# 15_PMU.net
KiCad netlist of a schematic drawn in Altium Designer
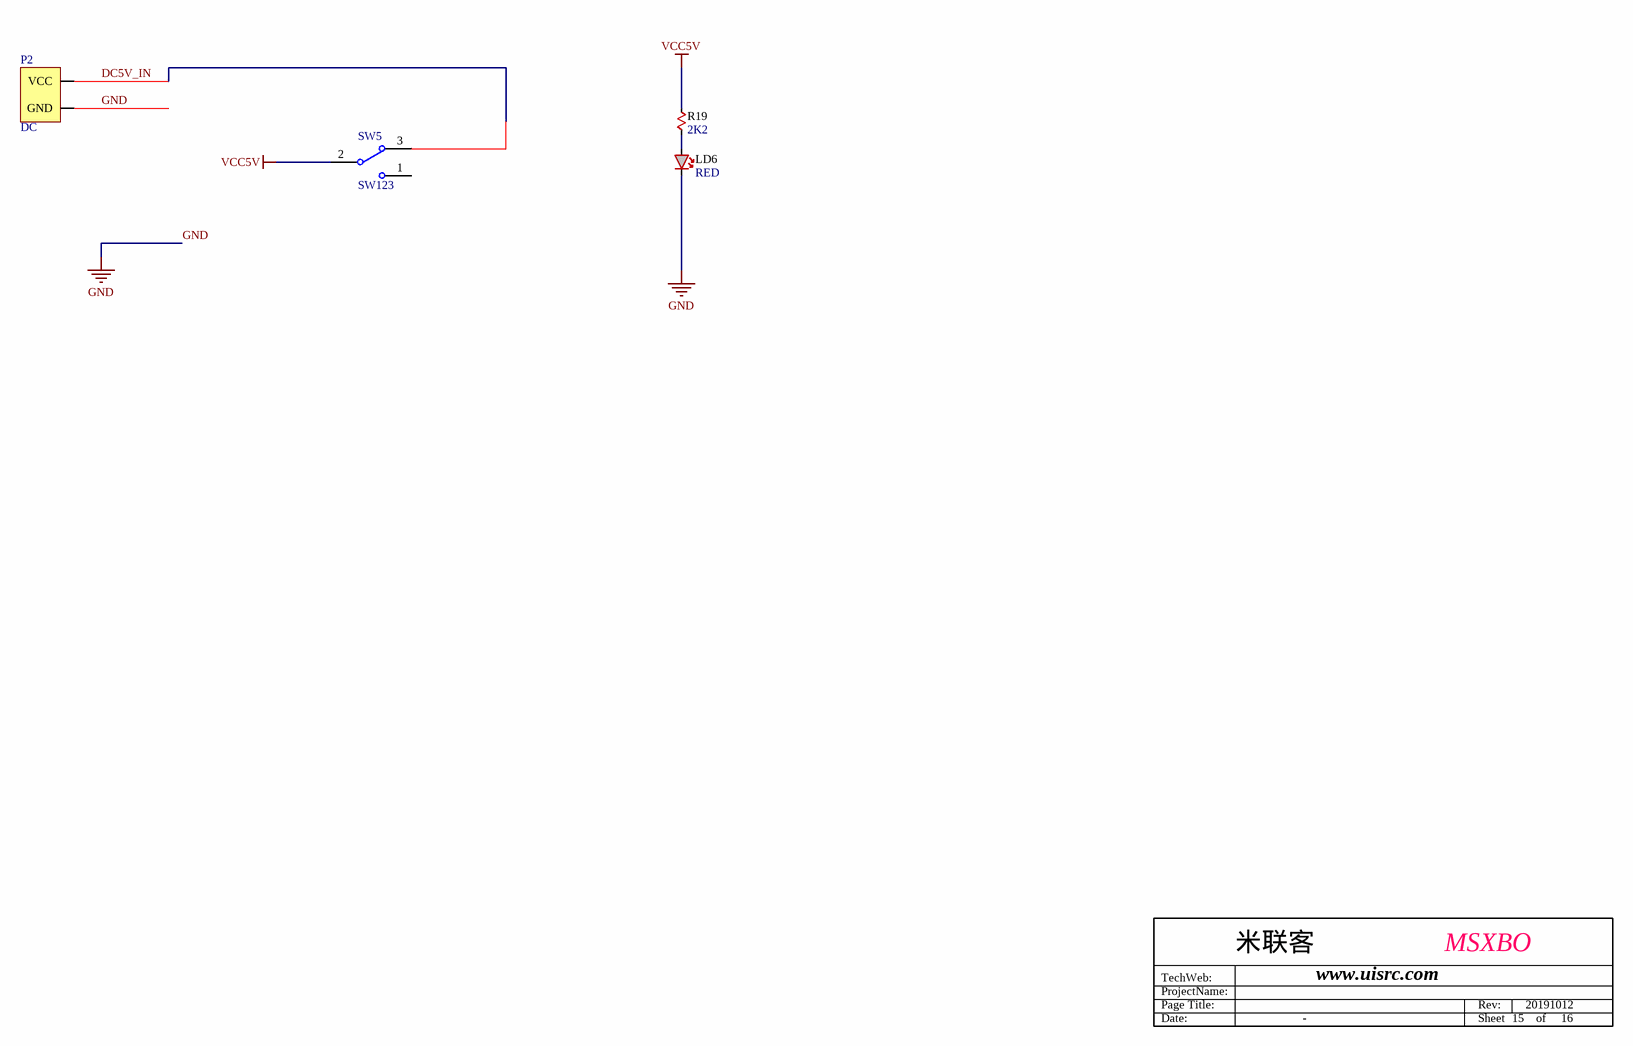
[diagram p0: 15_PMU.SchDoc]

(export (version "E")
  (design (tool "Eeschema 10.0.6"))
  (components
    (comp (ref "LD6")
      (value "RED")
      (footprint "D0603")
      (description "Generic LED")
      (fields (field (name "Comment") "LED"))
      (libsource (lib "Digilent") (part "LED"))
    )
    (comp (ref "P2") (value "DC") (footprint "DC5.0") (libsource (lib "jinrylib") (part "DC")))
    (comp (ref "R19")
      (value "2K2")
      (footprint "R0603")
      (description "Generic Resistor")
      (libsource (lib "Digilent") (part "RESISTOR"))
    )
    (comp (ref "SW5") (value "SW123") (footprint "SW1-2-3 -B") (libsource (lib "jinrylib") (part "SW123")))
  )
  (nets
    (net (code "1") (name "/DC5V_IN") (class "Default")
      (node (ref "P2") (pin "1") (pinfunction "VCC_1") (pintype "passive"))
      (node (ref "SW5") (pin "3") (pinfunction "3_3") (pintype "passive"))
    )
    (net (code "2") (name "GND") (class "Default")
      (node (ref "LD6") (pin "K") (pinfunction "K_K") (pintype "passive"))
      (node (ref "P2") (pin "2") (pinfunction "GND_2") (pintype "passive"))
    )
    (net (code "3") (name "Net-(LD6-PadA)") (class "Default")
      (node (ref "LD6") (pin "A") (pinfunction "A_A") (pintype "passive"))
      (node (ref "R19") (pin "2") (pinfunction "2_2") (pintype "passive"))
    )
    (net (code "4") (name "VCC5V") (class "Default")
      (node (ref "R19") (pin "1") (pinfunction "1_1") (pintype "passive"))
      (node (ref "SW5") (pin "2") (pinfunction "2_2") (pintype "passive"))
    )
    (net (code "5") (name "unconnected-(SW5-Pad1)") (class "Default")
      (node (ref "SW5") (pin "1") (pinfunction "1_1") (pintype "passive"))
    )
  )
)
